# Sheet1.net
KiCad netlist of a schematic drawn in Altium Designer
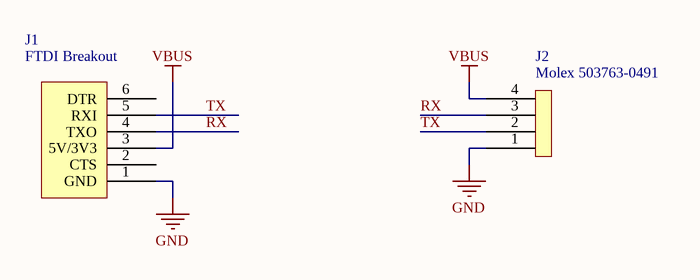
[diagram p0: Sheet1.SchDoc]

(export (version "E")
  (design (tool "Eeschema 10.0.6"))
  (components
    (comp (ref "J1")
      (value "FTDI Breakout")
      (footprint "FTDI Breakout")
      (libsource (lib "x-io") (part "FTDI Breakout"))
    )
    (comp (ref "J2")
      (value "Molex 503763-0491")
      (footprint "Molex 503763-0491")
      (libsource (lib "x-io") (part "Molex 503763-0491"))
    )
  )
  (nets
    (net (code "1") (name "/RX") (class "Default")
      (node (ref "J1") (pin "4") (pinfunction "TXO_4") (pintype "passive"))
      (node (ref "J2") (pin "3") (pinfunction "3_3") (pintype "passive"))
    )
    (net (code "2") (name "/TX") (class "Default")
      (node (ref "J1") (pin "5") (pinfunction "RXI_5") (pintype "passive"))
      (node (ref "J2") (pin "2") (pinfunction "2_2") (pintype "passive"))
    )
    (net (code "3") (name "GND") (class "Default")
      (node (ref "J1") (pin "1") (pinfunction "GND_1") (pintype "passive"))
      (node (ref "J2") (pin "1") (pinfunction "1_1") (pintype "passive"))
    )
    (net (code "4") (name "VBUS") (class "Default")
      (node (ref "J1") (pin "3") (pinfunction "5V/3V3_3") (pintype "passive"))
      (node (ref "J2") (pin "4") (pinfunction "4_4") (pintype "passive"))
    )
    (net (code "5") (name "unconnected-(J1-CTS-Pad2)") (class "Default")
      (node (ref "J1") (pin "2") (pinfunction "CTS_2") (pintype "passive"))
    )
    (net (code "6") (name "unconnected-(J1-DTR-Pad6)") (class "Default")
      (node (ref "J1") (pin "6") (pinfunction "DTR_6") (pintype "passive"))
    )
  )
)
